# BQ25895_Battery_Charger.net
KiCad netlist of a schematic drawn in Altium Designer
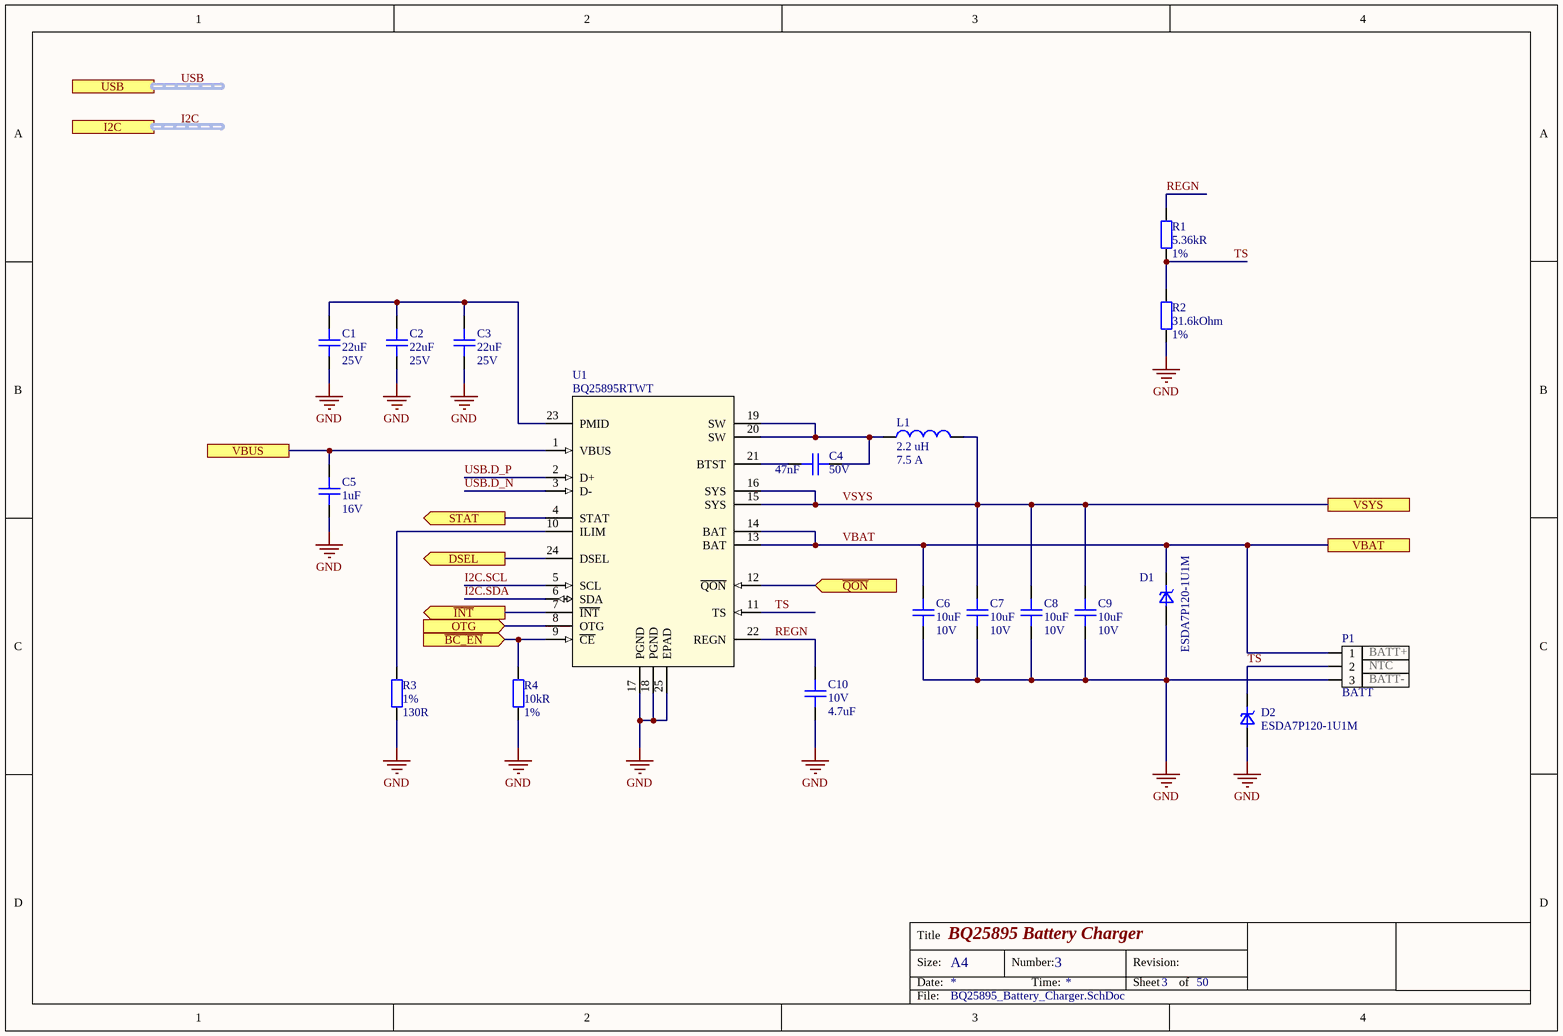
[diagram p0: BQ25895_Battery_Charger.SchDoc]

(export (version "E")
  (design (tool "Eeschema 10.0.6"))
  (components
    (comp (ref "C1")
      (value "CAP CER 22UF 25V X5R 0805")
      (footprint "C0805")
      (description "22µF ±20% 25V Ceramic Capacitor X5R 0805 (2012 Metric)")
      (fields
        (field (name "MANUFACTURER") "Yageo")
        (field (name "MANUFACTURER PART NUMBER") "CC0805MKX5R8BB226")
        (field (name "CAPACITANCE") "22uF")
        (field (name "VOLTAGE RATING") "25V")
      )
      (libsource (lib "Control_Board_Model") (part "CAP CER 22UF 25V X5R 0805"))
    )
    (comp (ref "C2")
      (value "CAP CER 22UF 25V X5R 0805")
      (footprint "C0805")
      (description "22µF ±20% 25V Ceramic Capacitor X5R 0805 (2012 Metric)")
      (fields
        (field (name "MANUFACTURER") "Yageo")
        (field (name "MANUFACTURER PART NUMBER") "CC0805MKX5R8BB226")
        (field (name "CAPACITANCE") "22uF")
        (field (name "VOLTAGE RATING") "25V")
      )
      (libsource (lib "Control_Board_Model") (part "CAP CER 22UF 25V X5R 0805"))
    )
    (comp (ref "C3")
      (value "CAP CER 22UF 25V X5R 0805")
      (footprint "C0805")
      (description "22µF ±20% 25V Ceramic Capacitor X5R 0805 (2012 Metric)")
      (fields
        (field (name "MANUFACTURER") "Yageo")
        (field (name "MANUFACTURER PART NUMBER") "CC0805MKX5R8BB226")
        (field (name "CAPACITANCE") "22uF")
        (field (name "VOLTAGE RATING") "25V")
      )
      (libsource (lib "Control_Board_Model") (part "CAP CER 22UF 25V X5R 0805"))
    )
    (comp (ref "C4")
      (value "CAP CER 0.047UF 50V X7R 0402")
      (footprint "C0402")
      (description "0.047µF ±10% 50V Ceramic Capacitor X7R 0402 (1005 Metric)")
      (fields
        (field (name "MANUFACTURER") "TDK")
        (field (name "MANUFACTURER PART NUMBER") "CGA2B3X7R1H473K050BB")
        (field (name "CAPACITANCE") "47nF")
        (field (name "VOLTAGE RATING") "50V")
      )
      (libsource (lib "capacitors_smd") (part "CAP CER 0.047UF 50V X7R 0402"))
    )
    (comp (ref "C5")
      (value "CAP CER 1UF 16V X5R 0603")
      (footprint "C0603")
      (description "1µF ±10% 16V Ceramic Capacitor X5R 0603 (1608 Metric)")
      (fields
        (field (name "MANUFACTURER") "Yageo")
        (field (name "MANUFACTURER PART NUMBER") "CC0603KRX5R7BB105")
        (field (name "CAPACITANCE") "1uF")
        (field (name "VOLTAGE RATING") "16V")
      )
      (libsource (lib "capacitors_smd") (part "CAP CER 1UF 16V X5R 0603"))
    )
    (comp (ref "C6")
      (value "CAP CER 10uF X7R 10% 0805")
      (footprint "C0805")
      (description "Capacitor,10uF,10V,X7R,10%,0805,Murata")
      (fields
        (field (name "MANUFACTURER") "Murata")
        (field (name "MANUFACTURER PART NUMBER") "GRM21BR71A106KA73L")
        (field (name "CAPACITANCE") "10uF")
        (field (name "VOLTAGE RATING") "10V")
      )
      (libsource (lib "capacitors_smd") (part "CAP CER 10uF X7R 10% 0805"))
    )
    (comp (ref "C7")
      (value "CAP CER 10uF X7R 10% 0805")
      (footprint "C0805")
      (description "Capacitor,10uF,10V,X7R,10%,0805,Murata")
      (fields
        (field (name "MANUFACTURER") "Murata")
        (field (name "MANUFACTURER PART NUMBER") "GRM21BR71A106KA73L")
        (field (name "CAPACITANCE") "10uF")
        (field (name "VOLTAGE RATING") "10V")
      )
      (libsource (lib "capacitors_smd") (part "CAP CER 10uF X7R 10% 0805"))
    )
    (comp (ref "C8")
      (value "CAP CER 10uF X7R 10% 0805")
      (footprint "C0805")
      (description "Capacitor,10uF,10V,X7R,10%,0805,Murata")
      (fields
        (field (name "MANUFACTURER") "Murata")
        (field (name "MANUFACTURER PART NUMBER") "GRM21BR71A106KA73L")
        (field (name "CAPACITANCE") "10uF")
        (field (name "VOLTAGE RATING") "10V")
      )
      (libsource (lib "capacitors_smd") (part "CAP CER 10uF X7R 10% 0805"))
    )
    (comp (ref "C9")
      (value "CAP CER 10uF X7R 10% 0805")
      (footprint "C0805")
      (description "Capacitor,10uF,10V,X7R,10%,0805,Murata")
      (fields
        (field (name "MANUFACTURER") "Murata")
        (field (name "MANUFACTURER PART NUMBER") "GRM21BR71A106KA73L")
        (field (name "CAPACITANCE") "10uF")
        (field (name "VOLTAGE RATING") "10V")
      )
      (libsource (lib "capacitors_smd") (part "CAP CER 10uF X7R 10% 0805"))
    )
    (comp (ref "C10")
      (value "CAP CER 4.7UF 10V X5R 0603")
      (footprint "C0603")
      (description "4.7µF ±10% 10V Ceramic Capacitor X5R 0603 (1608 Metric)")
      (fields
        (field (name "MANUFACTURER") "Yageo")
        (field (name "MANUFACTURER PART NUMBER") "CC0603KRX5R6BB475")
        (field (name "VOLTAGE RATING") "10V")
        (field (name "CAPACITANCE") "4.7uF")
      )
      (libsource (lib "capacitors_smd") (part "CAP CER 4.7UF 10V X5R 0603"))
    )
    (comp (ref "D1")
      (value "ESDA7P120-1U1M")
      (footprint "ST_QFN_1610")
      (description "11.5V Clamp 120A (8/20µs) Ipp Tvs Diode Surface Mount 1610")
      (fields (field (name "MANUFACTURER") "STMicroelectronics"))
      (libsource (lib "diodes_tvs") (part "TVS DIODE ESDA7P120-1U1M 5.5V 11.5V 1610"))
    )
    (comp (ref "D2")
      (value "ESDA7P120-1U1M")
      (footprint "ST_QFN_1610")
      (description "11.5V Clamp 120A (8/20µs) Ipp Tvs Diode Surface Mount 1610")
      (fields (field (name "MANUFACTURER") "STMicroelectronics"))
      (libsource (lib "diodes_tvs") (part "TVS DIODE ESDA7P120-1U1M 5.5V 11.5V 1610"))
    )
    (comp (ref "L1")
      (value "FIXED IND 2.2UH 7.5A 16.1MOHM SM")
      (footprint "IND_WE_MAPI")
      (description "2.2 µH Shielded - Inductor 7.5 A 16.1mOhm Max Nonstandard -")
      (fields
        (field (name "MANUFACTURER") "Wurth Elektronik")
        (field (name "MANUFACTURER PART NUMBER") "74438367022")
        (field (name "INDUCTANCE") "2.2 uH")
        (field (name "MAXIMUM DC CURRENT") "7.5 A")
      )
      (libsource (lib "Control_Board_Model") (part "FIXED IND 2.2UH 7.5A 16.1MOHM SM"))
    )
    (comp (ref "P1")
      (value "BATT")
      (footprint "CONN_JST_BM03B-AUHKS-GA-TB(LF)(SN)")
      (description "Connector Header Surface Mount, Right Angle 3 position")
      (fields
        (field (name "MANUFACTURER") "JST")
        (field (name "MANUFACTURER PART NUMBER") "BM03B-AUHKS-GA-TB(LF)(SN)")
        (field (name "PIN_1") "BATT+")
        (field (name "PIN_2") "NTC")
        (field (name "PIN_3") "BATT-")
      )
      (libsource (lib "Control_Board_Model") (part "CONN HEADER SMD R/A 3POS"))
    )
    (comp (ref "R1")
      (value "RES SMD 5.36K OHM 1% 1/16W 0402")
      (footprint "R0402")
      (description "5.36 kOhms ±1% 0.063W, 1/16W Chip Resistor 0402 (1005 Metric) Moisture Resistant Thick Film")
      (fields
        (field (name "MANUFACTURER PART NUMBER") "RC0402FR-075K36L")
        (field (name "MANUFACTURER") "Yageo")
        (field (name "RESISTANCE") "5.36kR")
        (field (name "TOLERANCE") "1%")
      )
      (libsource (lib "resistors_smd") (part "RES SMD 5.36K OHM 1% 1/16W 0402"))
    )
    (comp (ref "R2")
      (value "RES SMD 31.6K OHM 1% 1/16W 0402")
      (footprint "R0402")
      (description "31.6 kOhms ±1% 0.063W, 1/16W Chip Resistor 0402 (1005 Metric) Moisture Resistant Thick Film")
      (fields
        (field (name "MANUFACTURER PART NUMBER") "RC0402FR-0731K6L")
        (field (name "MANUFACTURER") "Yageo")
        (field (name "RESISTANCE") "31.6kOhm")
        (field (name "TOLERANCE") "1%")
      )
      (libsource (lib "resistors_smd") (part "RES SMD 31.6K OHM 1% 1/16W 0402"))
    )
    (comp (ref "R3")
      (value "RES SMD 130 OHM 1% 1/16W 0402")
      (footprint "R0402")
      (description "130 Ohms ±1% 0.063W, 1/16W Chip Resistor 0402 (1005 Metric) Moisture Resistant Thick Film")
      (fields
        (field (name "MANUFACTURER") "Yageo")
        (field (name "MANUFACTURER PART NUMBER") "RC0402FR-07130RL")
        (field (name "TOLERANCE") "1%")
        (field (name "RESISTANCE") "130R")
      )
      (libsource (lib "Control_Board_Model") (part "RES SMD 130 OHM 1% 1/16W 0402"))
    )
    (comp (ref "R4")
      (value "RES SMD 10K OHM 1% 1/16W 0402")
      (footprint "R0402")
      (description "10 kOhms ±1% 0.063W, 1/16W Chip Resistor 0402 (1005 Metric) Moisture Resistant Thick Film")
      (fields
        (field (name "MANUFACTURER PART NUMBER") "RC0402FR-0710KP")
        (field (name "MANUFACTURER") "Yageo")
        (field (name "RESISTANCE") "10kR")
        (field (name "TOLERANCE") "1%")
      )
      (libsource (lib "resistors_smd") (part "RES SMD 10K OHM 1% 1/16W 0402"))
    )
    (comp (ref "U1")
      (value "BQ25895RTWT")
      (footprint "WQFN-24")
      (description "Charger IC Lithium Ion/Polymer 24WQFN (4x4)")
      (fields (field (name "MANUFACTURER") "Texas Instruments"))
      (libsource (lib "Control_Board_Model") (part "IC BQ25895RTWT BATT CHG LI-ION 1CELL 24WQFN"))
    )
  )
  (nets
    (net (code "3") (name "/BC_EN") (class "Default")
      (node (ref "R4") (pin "1") (pinfunction "1_1") (pintype "passive"))
      (node (ref "U1") (pin "9") (pinfunction "~{CE}_9") (pintype "input"))
    )
    (net (code "4") (name "/DSEL") (class "Default")
      (node (ref "U1") (pin "24") (pinfunction "DSEL_24") (pintype "passive"))
    )
    (net (code "5") (name "/I2C.SCL") (class "Default")
      (node (ref "U1") (pin "5") (pinfunction "SCL_5") (pintype "input"))
    )
    (net (code "6") (name "/I2C.SDA") (class "Default")
      (node (ref "U1") (pin "6") (pinfunction "SDA_6") (pintype "bidirectional"))
    )
    (net (code "7") (name "/INT") (class "Default")
      (node (ref "U1") (pin "7") (pinfunction "INT_7") (pintype "open_collector"))
    )
    (net (code "8") (name "/OTG") (class "Default")
      (node (ref "U1") (pin "8") (pinfunction "OTG_8") (pintype "passive"))
    )
    (net (code "9") (name "/QON") (class "Default")
      (node (ref "U1") (pin "12") (pinfunction "~{QON}_12") (pintype "input"))
    )
    (net (code "10") (name "/REGN") (class "Default")
      (node (ref "C10") (pin "2") (pinfunction "2_2") (pintype "passive"))
      (node (ref "R1") (pin "1") (pinfunction "1_1") (pintype "passive"))
      (node (ref "U1") (pin "22") (pinfunction "REGN_22") (pintype "power_in"))
    )
    (net (code "11") (name "/STAT") (class "Default")
      (node (ref "U1") (pin "4") (pinfunction "STAT_4") (pintype "open_collector"))
    )
    (net (code "12") (name "/TS") (class "Default")
      (node (ref "D2") (pin "1") (pinfunction "K_1") (pintype "passive"))
      (node (ref "P1") (pin "2") (pinfunction "2_2") (pintype "passive"))
      (node (ref "R1") (pin "2") (pinfunction "2_2") (pintype "passive"))
      (node (ref "R2") (pin "2") (pinfunction "2_2") (pintype "passive"))
      (node (ref "U1") (pin "11") (pinfunction "TS_11") (pintype "input"))
    )
    (net (code "13") (name "/USB.D_N") (class "Default")
      (node (ref "U1") (pin "3") (pinfunction "D-_3") (pintype "input"))
    )
    (net (code "14") (name "/USB.D_P") (class "Default")
      (node (ref "U1") (pin "2") (pinfunction "D+_2") (pintype "input"))
    )
    (net (code "15") (name "/VBAT") (class "Default")
      (node (ref "C6") (pin "2") (pinfunction "2_2") (pintype "passive"))
      (node (ref "D1") (pin "1") (pinfunction "K_1") (pintype "passive"))
      (node (ref "P1") (pin "1") (pinfunction "1_1") (pintype "passive"))
      (node (ref "U1") (pin "13") (pinfunction "BAT_13") (pintype "power_in"))
      (node (ref "U1") (pin "14") (pinfunction "BAT_14") (pintype "power_in"))
    )
    (net (code "16") (name "/VBUS") (class "Default")
      (node (ref "C5") (pin "1") (pinfunction "1_1") (pintype "passive"))
      (node (ref "U1") (pin "1") (pinfunction "VBUS_1") (pintype "input"))
    )
    (net (code "17") (name "/VSYS") (class "Default")
      (node (ref "C7") (pin "2") (pinfunction "2_2") (pintype "passive"))
      (node (ref "C8") (pin "2") (pinfunction "2_2") (pintype "passive"))
      (node (ref "C9") (pin "2") (pinfunction "2_2") (pintype "passive"))
      (node (ref "L1") (pin "2") (pinfunction "2_2") (pintype "passive"))
      (node (ref "U1") (pin "15") (pinfunction "SYS_15") (pintype "power_in"))
      (node (ref "U1") (pin "16") (pinfunction "SYS_16") (pintype "power_in"))
    )
    (net (code "20") (name "GND") (class "Default")
      (node (ref "C1") (pin "1") (pinfunction "1_1") (pintype "passive"))
      (node (ref "C10") (pin "1") (pinfunction "1_1") (pintype "passive"))
      (node (ref "C2") (pin "1") (pinfunction "1_1") (pintype "passive"))
      (node (ref "C3") (pin "1") (pinfunction "1_1") (pintype "passive"))
      (node (ref "C5") (pin "2") (pinfunction "2_2") (pintype "passive"))
      (node (ref "C6") (pin "1") (pinfunction "1_1") (pintype "passive"))
      (node (ref "C7") (pin "1") (pinfunction "1_1") (pintype "passive"))
      (node (ref "C8") (pin "1") (pinfunction "1_1") (pintype "passive"))
      (node (ref "C9") (pin "1") (pinfunction "1_1") (pintype "passive"))
      (node (ref "D1") (pin "2") (pinfunction "A_2") (pintype "passive"))
      (node (ref "D2") (pin "2") (pinfunction "A_2") (pintype "passive"))
      (node (ref "P1") (pin "3") (pinfunction "3_3") (pintype "passive"))
      (node (ref "R2") (pin "1") (pinfunction "1_1") (pintype "passive"))
      (node (ref "R3") (pin "2") (pinfunction "2_2") (pintype "passive"))
      (node (ref "R4") (pin "2") (pinfunction "2_2") (pintype "passive"))
      (node (ref "U1") (pin "17") (pinfunction "PGND_17") (pintype "power_in"))
      (node (ref "U1") (pin "18") (pinfunction "PGND_18") (pintype "power_in"))
      (node (ref "U1") (pin "25") (pinfunction "EPAD_25") (pintype "power_in"))
    )
    (net (code "21") (name "Net-(C4-Pad2)") (class "Default")
      (node (ref "C4") (pin "2") (pinfunction "2_2") (pintype "passive"))
      (node (ref "L1") (pin "1") (pinfunction "1_1") (pintype "passive"))
      (node (ref "U1") (pin "19") (pinfunction "SW_19") (pintype "power_in"))
      (node (ref "U1") (pin "20") (pinfunction "SW_20") (pintype "power_in"))
    )
    (net (code "22") (name "Net-(U1-BTST)") (class "Default")
      (node (ref "C4") (pin "1") (pinfunction "1_1") (pintype "passive"))
      (node (ref "U1") (pin "21") (pinfunction "BTST_21") (pintype "power_in"))
    )
    (net (code "23") (name "Net-(U1-ILIM)") (class "Default")
      (node (ref "R3") (pin "1") (pinfunction "1_1") (pintype "passive"))
      (node (ref "U1") (pin "10") (pinfunction "ILIM_10") (pintype "passive"))
    )
    (net (code "24") (name "Net-(U1-PMID)") (class "Default")
      (node (ref "C1") (pin "2") (pinfunction "2_2") (pintype "passive"))
      (node (ref "C2") (pin "2") (pinfunction "2_2") (pintype "passive"))
      (node (ref "C3") (pin "2") (pinfunction "2_2") (pintype "passive"))
      (node (ref "U1") (pin "23") (pinfunction "PMID_23") (pintype "power_in"))
    )
  )
)
